# SCH_SilikonFM_2024-07-02.net
KiCad netlist of a schematic drawn in EasyEDA
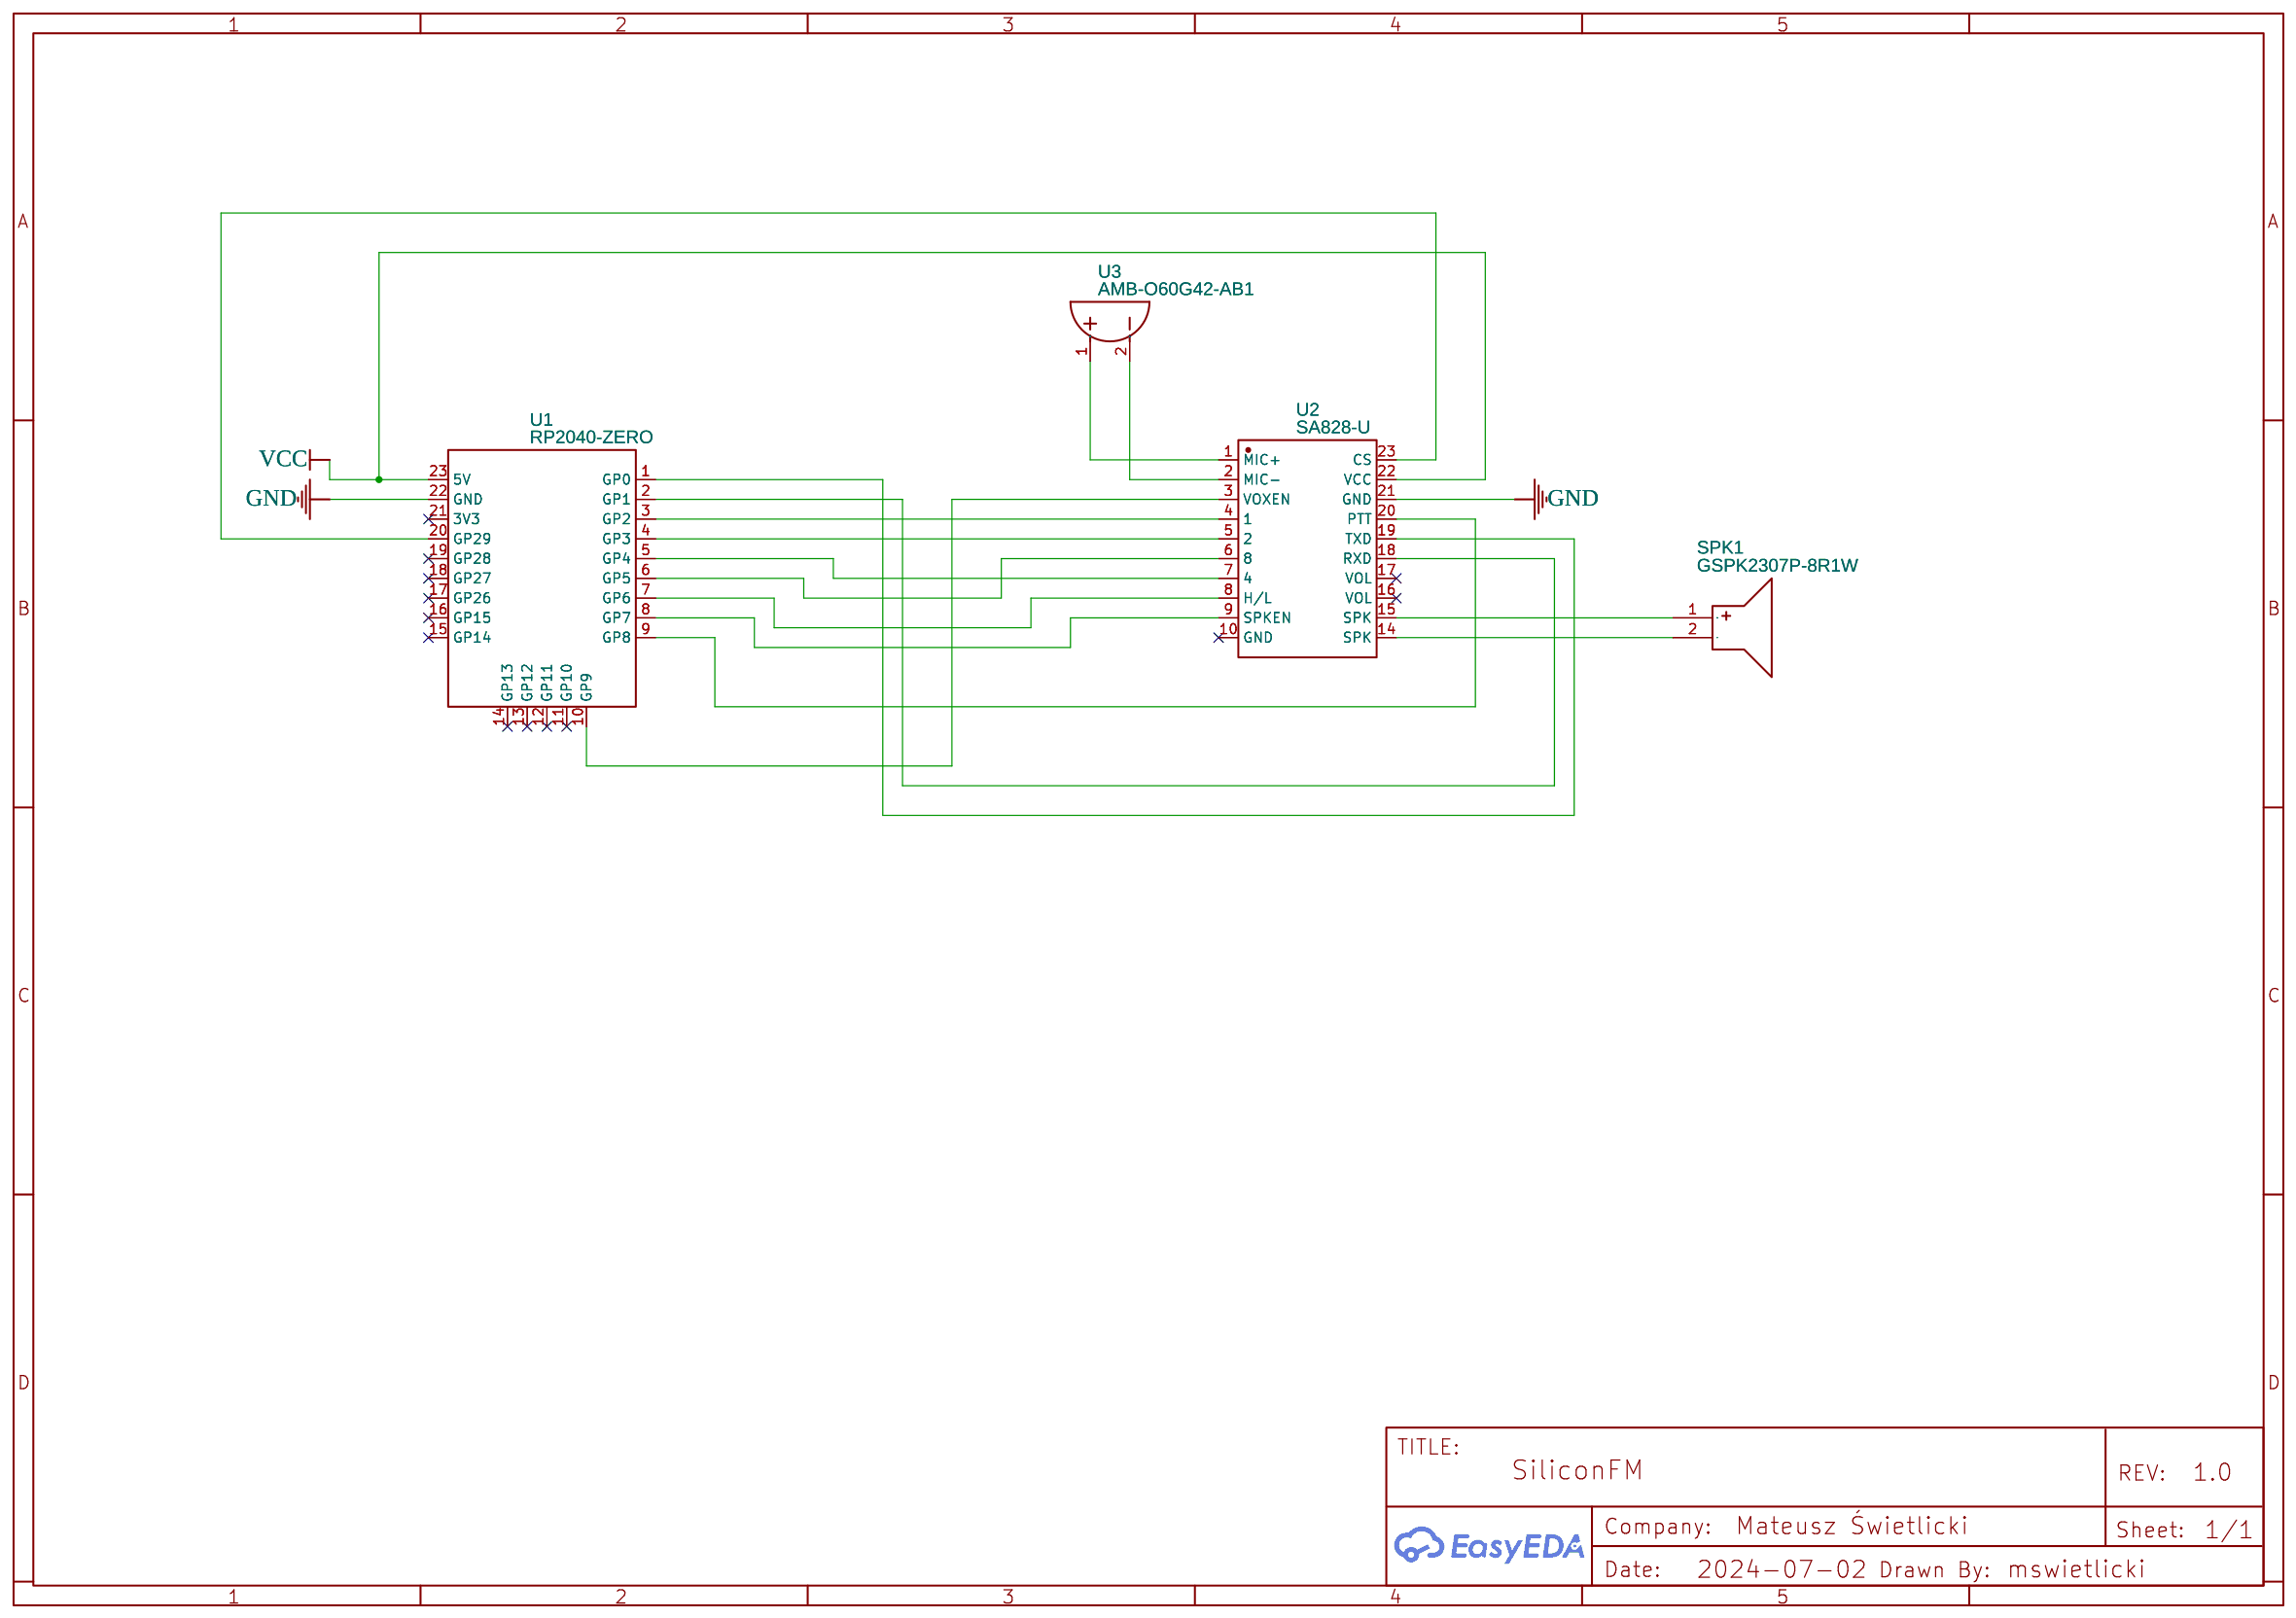
[diagram p0: schematic sheet]

(export (version "E")
  (design (tool "Eeschema 10.0.6"))
  (components
    (comp (ref "SPK1")
      (value "GSPK2307P-8R1W")
      (fields (field (name "Manufacturer") "INGHAi(赢海)"))
      (libsource (lib "") (part "GSPK2307P-8R1W"))
    )
    (comp (ref "U1")
      (value "RP2040-ZERO")
      (fields
        (field (name "Manufacturer Part") "RP2040-Zero")
        (field (name "Manufacturer") "Waveshare(微雪电子)")
      )
      (libsource (lib "") (part "RP2040-ZERO"))
    )
    (comp (ref "U2")
      (value "SA828-U")
      (fields (field (name "Manufacturer") "G-NiceRF(思为无线)"))
      (libsource (lib "") (part "SA828-U"))
    )
    (comp (ref "U3")
      (value "AMB-O60G42-AB1")
      (fields (field (name "Manufacturer") "Dragonstate(华龙)"))
      (libsource (lib "") (part "AMB-O60G42-AB1"))
    )
  )
  (nets
    (net (code "1") (name "GND") (class "Default")
      (node (ref "U1") (pin "22") (pinfunction "GND_22") (pintype "unspecified"))
      (node (ref "U2") (pin "21") (pinfunction "GND_21") (pintype "unspecified"))
    )
    (net (code "2") (name "Net-(SPK1-+)") (class "Default")
      (node (ref "SPK1") (pin "1") (pinfunction "+_1") (pintype "unspecified"))
      (node (ref "U2") (pin "15") (pinfunction "SPK_15") (pintype "unspecified"))
    )
    (net (code "3") (name "Net-(SPK1--)") (class "Default")
      (node (ref "SPK1") (pin "2") (pinfunction "-_2") (pintype "unspecified"))
      (node (ref "U2") (pin "14") (pinfunction "SPK_14") (pintype "unspecified"))
    )
    (net (code "4") (name "Net-(U1-GP0)") (class "Default")
      (node (ref "U1") (pin "1") (pinfunction "GP0_1") (pintype "unspecified"))
      (node (ref "U2") (pin "19") (pinfunction "TXD_19") (pintype "unspecified"))
    )
    (net (code "5") (name "Net-(U1-GP1)") (class "Default")
      (node (ref "U1") (pin "2") (pinfunction "GP1_2") (pintype "unspecified"))
      (node (ref "U2") (pin "18") (pinfunction "RXD_18") (pintype "unspecified"))
    )
    (net (code "6") (name "Net-(U1-GP2)") (class "Default")
      (node (ref "U1") (pin "3") (pinfunction "GP2_3") (pintype "unspecified"))
      (node (ref "U2") (pin "4") (pinfunction "1_4") (pintype "unspecified"))
    )
    (net (code "7") (name "Net-(U1-GP3)") (class "Default")
      (node (ref "U1") (pin "4") (pinfunction "GP3_4") (pintype "unspecified"))
      (node (ref "U2") (pin "5") (pinfunction "2_5") (pintype "unspecified"))
    )
    (net (code "8") (name "Net-(U1-GP4)") (class "Default")
      (node (ref "U1") (pin "5") (pinfunction "GP4_5") (pintype "unspecified"))
      (node (ref "U2") (pin "7") (pinfunction "4_7") (pintype "unspecified"))
    )
    (net (code "9") (name "Net-(U1-GP5)") (class "Default")
      (node (ref "U1") (pin "6") (pinfunction "GP5_6") (pintype "unspecified"))
      (node (ref "U2") (pin "6") (pinfunction "8_6") (pintype "unspecified"))
    )
    (net (code "10") (name "Net-(U1-GP6)") (class "Default")
      (node (ref "U1") (pin "7") (pinfunction "GP6_7") (pintype "unspecified"))
      (node (ref "U2") (pin "8") (pinfunction "H/L_8") (pintype "unspecified"))
    )
    (net (code "11") (name "Net-(U1-GP7)") (class "Default")
      (node (ref "U1") (pin "8") (pinfunction "GP7_8") (pintype "unspecified"))
      (node (ref "U2") (pin "9") (pinfunction "SPKEN_9") (pintype "unspecified"))
    )
    (net (code "12") (name "Net-(U1-GP8)") (class "Default")
      (node (ref "U1") (pin "9") (pinfunction "GP8_9") (pintype "unspecified"))
      (node (ref "U2") (pin "20") (pinfunction "PTT_20") (pintype "unspecified"))
    )
    (net (code "13") (name "Net-(U1-GP9)") (class "Default")
      (node (ref "U1") (pin "10") (pinfunction "GP9_10") (pintype "unspecified"))
      (node (ref "U2") (pin "3") (pinfunction "VOXEN_3") (pintype "unspecified"))
    )
    (net (code "14") (name "Net-(U1-GP29)") (class "Default")
      (node (ref "U1") (pin "20") (pinfunction "GP29_20") (pintype "unspecified"))
      (node (ref "U2") (pin "23") (pinfunction "CS_23") (pintype "unspecified"))
    )
    (net (code "15") (name "Net-(U2-MIC+)") (class "Default")
      (node (ref "U2") (pin "1") (pinfunction "MIC+_1") (pintype "unspecified"))
      (node (ref "U3") (pin "1") (pinfunction "1_1") (pintype "unspecified"))
    )
    (net (code "16") (name "Net-(U2-MIC-)") (class "Default")
      (node (ref "U2") (pin "2") (pinfunction "MIC-_2") (pintype "unspecified"))
      (node (ref "U3") (pin "2") (pinfunction "2_2") (pintype "unspecified"))
    )
    (net (code "17") (name "VCC") (class "Default")
      (node (ref "U1") (pin "23") (pinfunction "5V_23") (pintype "unspecified"))
      (node (ref "U2") (pin "22") (pinfunction "VCC_22") (pintype "unspecified"))
    )
    (net (code "18") (name "unconnected-(U1-3V3-Pad21)") (class "Default")
      (node (ref "U1") (pin "21") (pinfunction "3V3_21") (pintype "unspecified+no_connect"))
    )
    (net (code "19") (name "unconnected-(U1-GP10-Pad11)") (class "Default")
      (node (ref "U1") (pin "11") (pinfunction "GP10_11") (pintype "unspecified+no_connect"))
    )
    (net (code "20") (name "unconnected-(U1-GP11-Pad12)") (class "Default")
      (node (ref "U1") (pin "12") (pinfunction "GP11_12") (pintype "unspecified+no_connect"))
    )
    (net (code "21") (name "unconnected-(U1-GP12-Pad13)") (class "Default")
      (node (ref "U1") (pin "13") (pinfunction "GP12_13") (pintype "unspecified+no_connect"))
    )
    (net (code "22") (name "unconnected-(U1-GP13-Pad14)") (class "Default")
      (node (ref "U1") (pin "14") (pinfunction "GP13_14") (pintype "unspecified+no_connect"))
    )
    (net (code "23") (name "unconnected-(U1-GP14-Pad15)") (class "Default")
      (node (ref "U1") (pin "15") (pinfunction "GP14_15") (pintype "unspecified+no_connect"))
    )
    (net (code "24") (name "unconnected-(U1-GP15-Pad16)") (class "Default")
      (node (ref "U1") (pin "16") (pinfunction "GP15_16") (pintype "unspecified+no_connect"))
    )
    (net (code "25") (name "unconnected-(U1-GP26-Pad17)") (class "Default")
      (node (ref "U1") (pin "17") (pinfunction "GP26_17") (pintype "unspecified+no_connect"))
    )
    (net (code "26") (name "unconnected-(U1-GP27-Pad18)") (class "Default")
      (node (ref "U1") (pin "18") (pinfunction "GP27_18") (pintype "unspecified+no_connect"))
    )
    (net (code "27") (name "unconnected-(U1-GP28-Pad19)") (class "Default")
      (node (ref "U1") (pin "19") (pinfunction "GP28_19") (pintype "unspecified+no_connect"))
    )
    (net (code "28") (name "unconnected-(U2-GND-Pad10)") (class "Default")
      (node (ref "U2") (pin "10") (pinfunction "GND_10") (pintype "unspecified+no_connect"))
    )
    (net (code "29") (name "unconnected-(U2-VOL-Pad16)") (class "Default")
      (node (ref "U2") (pin "16") (pinfunction "VOL_16") (pintype "unspecified+no_connect"))
    )
    (net (code "30") (name "unconnected-(U2-VOL-Pad17)") (class "Default")
      (node (ref "U2") (pin "17") (pinfunction "VOL_17") (pintype "unspecified+no_connect"))
    )
  )
)
